# SpiderHand_BendLabs.net
KiCad netlist of a schematic drawn in EAGLE
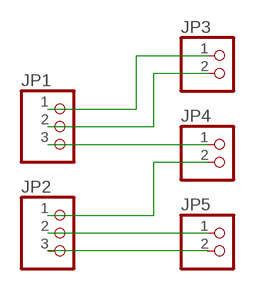
[diagram p0: schematic, sheet 1]

(export (version "E")
  (design (tool "Eeschema 10.0.6"))
  (components
    (comp (ref "JP1")
      (value "PINHD-1X3")
      (footprint "eagle-import:1X03")
      (libsource (lib "eagle-import") (part "PINHD-1X3"))
    )
    (comp (ref "JP2")
      (value "PINHD-1X3")
      (footprint "eagle-import:1X03")
      (libsource (lib "eagle-import") (part "PINHD-1X3"))
    )
    (comp (ref "JP3")
      (value "PINHD-1X2")
      (footprint "eagle-import:1X02")
      (libsource (lib "eagle-import") (part "PINHD-1X2"))
    )
    (comp (ref "JP4")
      (value "PINHD-1X2")
      (footprint "eagle-import:1X02")
      (libsource (lib "eagle-import") (part "PINHD-1X2"))
    )
    (comp (ref "JP5")
      (value "PINHD-1X2")
      (footprint "eagle-import:1X02")
      (libsource (lib "eagle-import") (part "PINHD-1X2"))
    )
  )
  (nets
    (net (code "1") (name "Net-(JP1-Pad1)") (class "Default")
      (node (ref "JP1") (pin "1") (pinfunction "1_1") (pintype "passive"))
      (node (ref "JP3") (pin "1") (pinfunction "1_1") (pintype "passive"))
    )
    (net (code "2") (name "Net-(JP1-Pad2)") (class "Default")
      (node (ref "JP1") (pin "2") (pinfunction "2_2") (pintype "passive"))
      (node (ref "JP3") (pin "2") (pinfunction "2_2") (pintype "passive"))
    )
    (net (code "3") (name "Net-(JP1-Pad3)") (class "Default")
      (node (ref "JP1") (pin "3") (pinfunction "3_3") (pintype "passive"))
      (node (ref "JP4") (pin "1") (pinfunction "1_1") (pintype "passive"))
    )
    (net (code "4") (name "Net-(JP2-Pad1)") (class "Default")
      (node (ref "JP2") (pin "1") (pinfunction "1_1") (pintype "passive"))
      (node (ref "JP4") (pin "2") (pinfunction "2_2") (pintype "passive"))
    )
    (net (code "5") (name "Net-(JP2-Pad2)") (class "Default")
      (node (ref "JP2") (pin "2") (pinfunction "2_2") (pintype "passive"))
      (node (ref "JP5") (pin "1") (pinfunction "1_1") (pintype "passive"))
    )
    (net (code "6") (name "Net-(JP2-Pad3)") (class "Default")
      (node (ref "JP2") (pin "3") (pinfunction "3_3") (pintype "passive"))
      (node (ref "JP5") (pin "2") (pinfunction "2_2") (pintype "passive"))
    )
  )
)
